# HirigrandeCHINA_V2_1.net
KiCad netlist of a schematic drawn in EAGLE
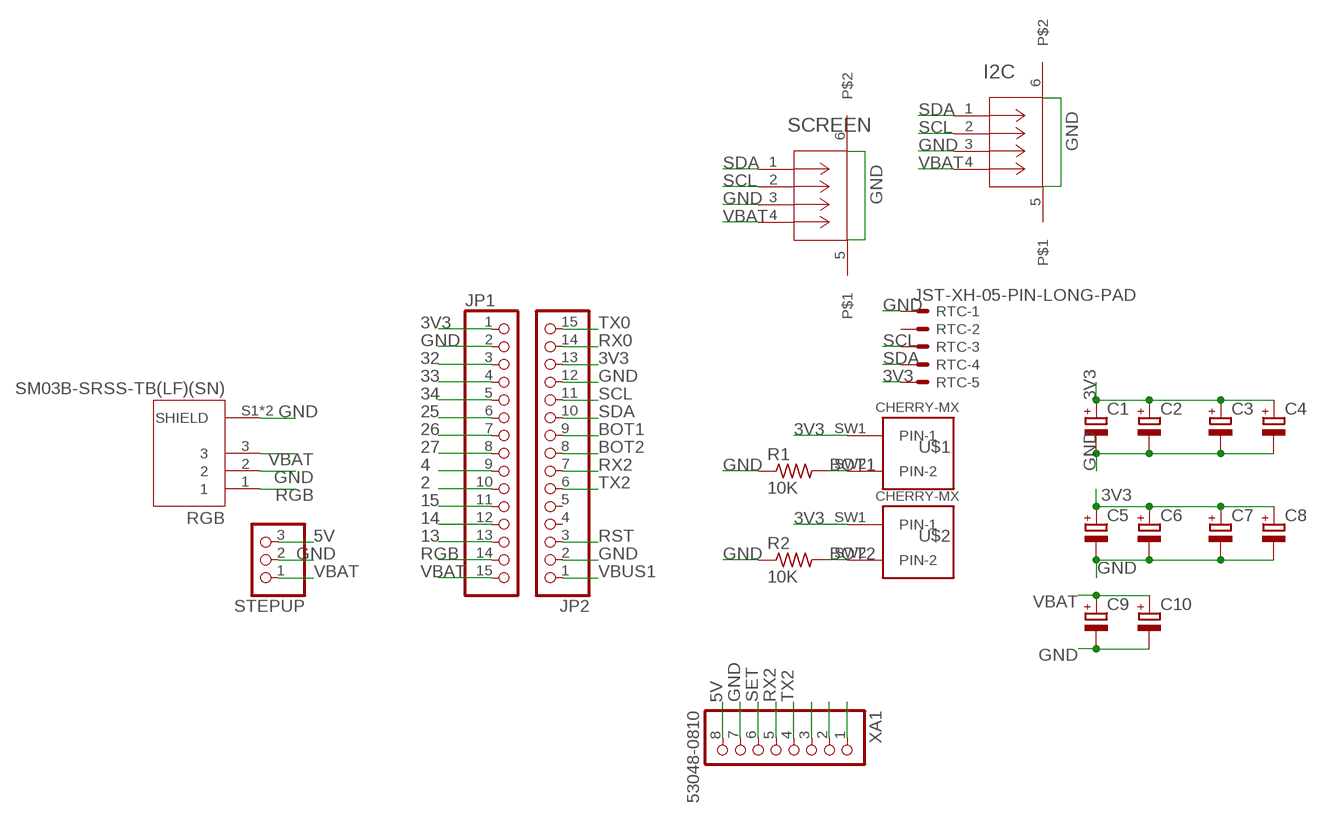
[diagram p0: schematic, sheet 1]

(export (version "E")
  (design (tool "Eeschema 10.0.6"))
  (components
    (comp (ref "C1")
      (value "CPOL-EUSMCD")
      (footprint "eagle-import:SMC_D")
      (libsource (lib "eagle-import") (part "CPOL-EUSMCD"))
    )
    (comp (ref "C2")
      (value "CPOL-EUSMCD")
      (footprint "eagle-import:SMC_D")
      (libsource (lib "eagle-import") (part "CPOL-EUSMCD"))
    )
    (comp (ref "C3")
      (value "CPOL-EUSMCD")
      (footprint "eagle-import:SMC_D")
      (libsource (lib "eagle-import") (part "CPOL-EUSMCD"))
    )
    (comp (ref "C4")
      (value "CPOL-EUSMCD")
      (footprint "eagle-import:SMC_D")
      (libsource (lib "eagle-import") (part "CPOL-EUSMCD"))
    )
    (comp (ref "C5")
      (value "CPOL-EUSMCD")
      (footprint "eagle-import:SMC_D")
      (libsource (lib "eagle-import") (part "CPOL-EUSMCD"))
    )
    (comp (ref "C6")
      (value "CPOL-EUSMCD")
      (footprint "eagle-import:SMC_D")
      (libsource (lib "eagle-import") (part "CPOL-EUSMCD"))
    )
    (comp (ref "C7")
      (value "CPOL-EUSMCD")
      (footprint "eagle-import:SMC_D")
      (libsource (lib "eagle-import") (part "CPOL-EUSMCD"))
    )
    (comp (ref "C8")
      (value "CPOL-EUSMCD")
      (footprint "eagle-import:SMC_D")
      (libsource (lib "eagle-import") (part "CPOL-EUSMCD"))
    )
    (comp (ref "C9")
      (value "CPOL-EUSMCD")
      (footprint "eagle-import:SMC_D")
      (libsource (lib "eagle-import") (part "CPOL-EUSMCD"))
    )
    (comp (ref "C10")
      (value "CPOL-EUSMCD")
      (footprint "eagle-import:SMC_D")
      (libsource (lib "eagle-import") (part "CPOL-EUSMCD"))
    )
    (comp (ref "I2C")
      (value "SM04B-SRSS-TB")
      (footprint "eagle-import:CONN_SM04B-SRSS-TB_JST")
      (fields (field (name "MF") "JST Sales"))
      (libsource (lib "eagle-import") (part "SM04B-SRSS-TB"))
    )
    (comp (ref "JP1")
      (value "PINHD-1X15")
      (footprint "eagle-import:1X15")
      (libsource (lib "eagle-import") (part "PINHD-1X15"))
    )
    (comp (ref "JP2")
      (value "PINHD-1X15")
      (footprint "eagle-import:1X15")
      (libsource (lib "eagle-import") (part "PINHD-1X15"))
    )
    (comp (ref "R1")
      (value "10K")
      (footprint "eagle-import:0204_7")
      (libsource (lib "eagle-import") (part "R-US_0204/7"))
    )
    (comp (ref "R2")
      (value "10K")
      (footprint "eagle-import:0204_7")
      (libsource (lib "eagle-import") (part "R-US_0204/7"))
    )
    (comp (ref "RGB")
      (value "SM03B-SRSS-TB(LF)(SN)")
      (footprint "eagle-import:JST_SM03B-SRSS-TB(LF)(SN)")
      (fields (field (name "MF") "JST Sales America Inc."))
      (libsource (lib "eagle-import") (part "SM03B-SRSS-TB(LF)(SN)"))
    )
    (comp (ref "RTC")
      (value "JST-XH-05-PIN-LONG-PAD")
      (footprint "eagle-import:JST-XH-05-PACKAGE-LONG-PAD")
      (libsource (lib "eagle-import") (part "JST-XH-05-PIN-LONG-PAD"))
    )
    (comp (ref "SCREEN")
      (value "SM04B-SRSS-TB")
      (footprint "eagle-import:CONN_SM04B-SRSS-TB_JST")
      (fields (field (name "MF") "JST Sales"))
      (libsource (lib "eagle-import") (part "SM04B-SRSS-TB"))
    )
    (comp (ref "STEPUP")
      (value "PINHD-1X3")
      (footprint "eagle-import:1X03")
      (libsource (lib "eagle-import") (part "PINHD-1X3"))
    )
    (comp (ref "U$1")
      (value "CHERRY-MX")
      (footprint "eagle-import:CHERRY-MX")
      (libsource (lib "eagle-import") (part "CHERRY-MX"))
    )
    (comp (ref "U$2")
      (value "CHERRY-MX")
      (footprint "eagle-import:CHERRY-MX")
      (libsource (lib "eagle-import") (part "CHERRY-MX"))
    )
    (comp (ref "XA1")
      (value "53048-0810")
      (footprint "eagle-import:MOLEX_53048-0810")
      (fields (field (name "MF") "Molex"))
      (libsource (lib "eagle-import") (part "53048-0810"))
    )
  )
  (nets
    (net (code "1") (name "/2") (class "Default")
      (node (ref "JP1") (pin "10") (pinfunction "10_10") (pintype "passive"))
    )
    (net (code "2") (name "/3V3") (class "Default")
      (node (ref "C1") (pin "+") (pinfunction "+_+") (pintype "passive"))
      (node (ref "C2") (pin "+") (pinfunction "+_+") (pintype "passive"))
      (node (ref "C3") (pin "+") (pinfunction "+_+") (pintype "passive"))
      (node (ref "C4") (pin "+") (pinfunction "+_+") (pintype "passive"))
      (node (ref "C5") (pin "+") (pinfunction "+_+") (pintype "passive"))
      (node (ref "C6") (pin "+") (pinfunction "+_+") (pintype "passive"))
      (node (ref "C7") (pin "+") (pinfunction "+_+") (pintype "passive"))
      (node (ref "C8") (pin "+") (pinfunction "+_+") (pintype "passive"))
      (node (ref "JP1") (pin "1") (pinfunction "1_1") (pintype "passive"))
      (node (ref "JP2") (pin "13") (pinfunction "13_13") (pintype "passive"))
      (node (ref "RTC") (pin "5") (pinfunction "S_5") (pintype "passive"))
      (node (ref "U$1") (pin "SW1") (pinfunction "PIN-1_SW1") (pintype "bidirectional"))
      (node (ref "U$2") (pin "SW1") (pinfunction "PIN-1_SW1") (pintype "bidirectional"))
    )
    (net (code "3") (name "/4") (class "Default")
      (node (ref "JP1") (pin "9") (pinfunction "9_9") (pintype "passive"))
    )
    (net (code "4") (name "/5V") (class "Default")
      (node (ref "STEPUP") (pin "3") (pinfunction "3_3") (pintype "passive"))
      (node (ref "XA1") (pin "8") (pinfunction "8_8") (pintype "passive"))
    )
    (net (code "5") (name "/13") (class "Default")
      (node (ref "JP1") (pin "13") (pinfunction "13_13") (pintype "passive"))
    )
    (net (code "6") (name "/14") (class "Default")
      (node (ref "JP1") (pin "12") (pinfunction "12_12") (pintype "passive"))
    )
    (net (code "7") (name "/15") (class "Default")
      (node (ref "JP1") (pin "11") (pinfunction "11_11") (pintype "passive"))
    )
    (net (code "8") (name "/25") (class "Default")
      (node (ref "JP1") (pin "6") (pinfunction "6_6") (pintype "passive"))
    )
    (net (code "9") (name "/26") (class "Default")
      (node (ref "JP1") (pin "7") (pinfunction "7_7") (pintype "passive"))
    )
    (net (code "10") (name "/27") (class "Default")
      (node (ref "JP1") (pin "8") (pinfunction "8_8") (pintype "passive"))
    )
    (net (code "11") (name "/32") (class "Default")
      (node (ref "JP1") (pin "3") (pinfunction "3_3") (pintype "passive"))
    )
    (net (code "12") (name "/33") (class "Default")
      (node (ref "JP1") (pin "4") (pinfunction "4_4") (pintype "passive"))
    )
    (net (code "13") (name "/34") (class "Default")
      (node (ref "JP1") (pin "5") (pinfunction "5_5") (pintype "passive"))
    )
    (net (code "14") (name "/BOT1") (class "Default")
      (node (ref "JP2") (pin "9") (pinfunction "9_9") (pintype "passive"))
      (node (ref "R1") (pin "2") (pinfunction "2_2") (pintype "passive"))
      (node (ref "U$1") (pin "SW2") (pinfunction "PIN-2_SW2") (pintype "bidirectional"))
    )
    (net (code "15") (name "/BOT2") (class "Default")
      (node (ref "JP2") (pin "8") (pinfunction "8_8") (pintype "passive"))
      (node (ref "R2") (pin "2") (pinfunction "2_2") (pintype "passive"))
      (node (ref "U$2") (pin "SW2") (pinfunction "PIN-2_SW2") (pintype "bidirectional"))
    )
    (net (code "16") (name "/GND") (class "Default")
      (node (ref "C1") (pin "-") (pinfunction "-_-") (pintype "passive"))
      (node (ref "C10") (pin "-") (pinfunction "-_-") (pintype "passive"))
      (node (ref "C2") (pin "-") (pinfunction "-_-") (pintype "passive"))
      (node (ref "C3") (pin "-") (pinfunction "-_-") (pintype "passive"))
      (node (ref "C4") (pin "-") (pinfunction "-_-") (pintype "passive"))
      (node (ref "C5") (pin "-") (pinfunction "-_-") (pintype "passive"))
      (node (ref "C6") (pin "-") (pinfunction "-_-") (pintype "passive"))
      (node (ref "C7") (pin "-") (pinfunction "-_-") (pintype "passive"))
      (node (ref "C8") (pin "-") (pinfunction "-_-") (pintype "passive"))
      (node (ref "C9") (pin "-") (pinfunction "-_-") (pintype "passive"))
      (node (ref "I2C") (pin "3") (pinfunction "3_3") (pintype "passive"))
      (node (ref "I2C") (pin "5") (pinfunction "P$1_5") (pintype "bidirectional"))
      (node (ref "I2C") (pin "6") (pinfunction "P$2_6") (pintype "bidirectional"))
      (node (ref "JP1") (pin "2") (pinfunction "2_2") (pintype "passive"))
      (node (ref "JP2") (pin "12") (pinfunction "12_12") (pintype "passive"))
      (node (ref "JP2") (pin "2") (pinfunction "2_2") (pintype "passive"))
      (node (ref "R1") (pin "1") (pinfunction "1_1") (pintype "passive"))
      (node (ref "R2") (pin "1") (pinfunction "1_1") (pintype "passive"))
      (node (ref "RGB") (pin "2") (pinfunction "2_2") (pintype "passive"))
      (node (ref "RGB") (pin "S1") (pinfunction "SHIELD_S1") (pintype "passive"))
      (node (ref "RGB") (pin "S2") (pinfunction "SHIELD_S2") (pintype "passive"))
      (node (ref "RTC") (pin "1") (pinfunction "S_1") (pintype "passive"))
      (node (ref "SCREEN") (pin "3") (pinfunction "3_3") (pintype "passive"))
      (node (ref "SCREEN") (pin "5") (pinfunction "P$1_5") (pintype "bidirectional"))
      (node (ref "SCREEN") (pin "6") (pinfunction "P$2_6") (pintype "bidirectional"))
      (node (ref "STEPUP") (pin "2") (pinfunction "2_2") (pintype "passive"))
      (node (ref "XA1") (pin "7") (pinfunction "7_7") (pintype "passive"))
    )
    (net (code "17") (name "/RGB") (class "Default")
      (node (ref "JP1") (pin "14") (pinfunction "14_14") (pintype "passive"))
      (node (ref "RGB") (pin "1") (pinfunction "1_1") (pintype "passive"))
    )
    (net (code "18") (name "/RST") (class "Default")
      (node (ref "JP2") (pin "3") (pinfunction "3_3") (pintype "passive"))
    )
    (net (code "19") (name "/RX0") (class "Default")
      (node (ref "JP2") (pin "14") (pinfunction "14_14") (pintype "passive"))
    )
    (net (code "20") (name "/RX2") (class "Default")
      (node (ref "JP2") (pin "7") (pinfunction "7_7") (pintype "passive"))
      (node (ref "XA1") (pin "5") (pinfunction "5_5") (pintype "passive"))
    )
    (net (code "21") (name "/SCL") (class "Default")
      (node (ref "I2C") (pin "2") (pinfunction "2_2") (pintype "passive"))
      (node (ref "JP2") (pin "11") (pinfunction "11_11") (pintype "passive"))
      (node (ref "RTC") (pin "3") (pinfunction "S_3") (pintype "passive"))
      (node (ref "SCREEN") (pin "2") (pinfunction "2_2") (pintype "passive"))
    )
    (net (code "22") (name "/SDA") (class "Default")
      (node (ref "I2C") (pin "1") (pinfunction "1_1") (pintype "passive"))
      (node (ref "JP2") (pin "10") (pinfunction "10_10") (pintype "passive"))
      (node (ref "RTC") (pin "4") (pinfunction "S_4") (pintype "passive"))
      (node (ref "SCREEN") (pin "1") (pinfunction "1_1") (pintype "passive"))
    )
    (net (code "23") (name "/SET") (class "Default")
      (node (ref "XA1") (pin "6") (pinfunction "6_6") (pintype "passive"))
    )
    (net (code "24") (name "/TX0") (class "Default")
      (node (ref "JP2") (pin "15") (pinfunction "15_15") (pintype "passive"))
    )
    (net (code "25") (name "/TX2") (class "Default")
      (node (ref "JP2") (pin "6") (pinfunction "6_6") (pintype "passive"))
      (node (ref "XA1") (pin "4") (pinfunction "4_4") (pintype "passive"))
    )
    (net (code "26") (name "/VBAT") (class "Default")
      (node (ref "C10") (pin "+") (pinfunction "+_+") (pintype "passive"))
      (node (ref "C9") (pin "+") (pinfunction "+_+") (pintype "passive"))
      (node (ref "I2C") (pin "4") (pinfunction "4_4") (pintype "passive"))
      (node (ref "JP1") (pin "15") (pinfunction "15_15") (pintype "passive"))
      (node (ref "RGB") (pin "3") (pinfunction "3_3") (pintype "passive"))
      (node (ref "SCREEN") (pin "4") (pinfunction "4_4") (pintype "passive"))
      (node (ref "STEPUP") (pin "1") (pinfunction "1_1") (pintype "passive"))
    )
    (net (code "27") (name "/VBUS1") (class "Default")
      (node (ref "JP2") (pin "1") (pinfunction "1_1") (pintype "passive"))
    )
    (net (code "28") (name "unconnected-(JP2-Pad4)") (class "Default")
      (node (ref "JP2") (pin "4") (pinfunction "4_4") (pintype "passive"))
    )
    (net (code "29") (name "unconnected-(JP2-Pad5)") (class "Default")
      (node (ref "JP2") (pin "5") (pinfunction "5_5") (pintype "passive"))
    )
    (net (code "30") (name "unconnected-(RTCB-S-Pad2)") (class "Default")
      (node (ref "RTC") (pin "2") (pinfunction "S_2") (pintype "passive"))
    )
    (net (code "31") (name "unconnected-(XA1-Pad1)") (class "Default")
      (node (ref "XA1") (pin "1") (pinfunction "1_1") (pintype "passive"))
    )
    (net (code "32") (name "unconnected-(XA1-Pad2)") (class "Default")
      (node (ref "XA1") (pin "2") (pinfunction "2_2") (pintype "passive"))
    )
    (net (code "33") (name "unconnected-(XA1-Pad3)") (class "Default")
      (node (ref "XA1") (pin "3") (pinfunction "3_3") (pintype "passive"))
    )
  )
)
